# JanusV1.net
KiCad netlist of a schematic drawn in EAGLE
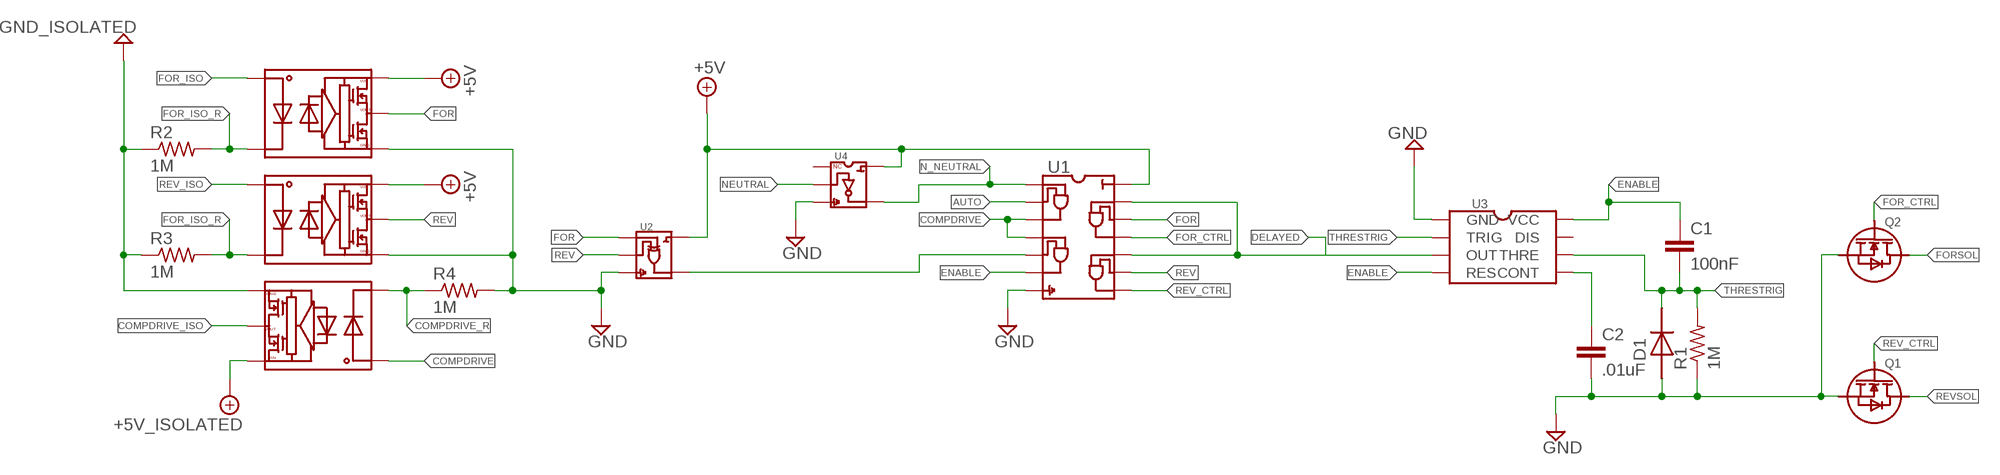
[diagram p0: schematic, sheet 1]

(export (version "E")
  (design (tool "Eeschema 10.0.6"))
  (components
    (comp (ref "C1")
      (value "100nF")
      (footprint "eagle-import:C0603")
      (libsource (lib "eagle-import") (part "C-EUC0603"))
    )
    (comp (ref "C2")
      (value ".01uF")
      (footprint "eagle-import:C0603")
      (libsource (lib "eagle-import") (part "C-EUC0603"))
    )
    (comp (ref "D1")
      (value "1N4148X-TP")
      (footprint "eagle-import:SOD523_SC79")
      (libsource (lib "eagle-import") (part "1N4148X-TP"))
    )
    (comp (ref "OK1")
      (value "TLP152")
      (footprint "eagle-import:6-SOIC-5")
      (libsource (lib "eagle-import") (part "TLP152"))
    )
    (comp (ref "OK2")
      (value "TLP152")
      (footprint "eagle-import:6-SOIC-5")
      (libsource (lib "eagle-import") (part "TLP152"))
    )
    (comp (ref "OK3")
      (value "TLP152")
      (footprint "eagle-import:6-SOIC-5")
      (libsource (lib "eagle-import") (part "TLP152"))
    )
    (comp (ref "Q1")
      (value "DMN6140L-7")
      (footprint "eagle-import:SOT23")
      (libsource (lib "eagle-import") (part "DMN6140L-7"))
    )
    (comp (ref "Q2")
      (value "DMN6140L-7")
      (footprint "eagle-import:SOT23")
      (libsource (lib "eagle-import") (part "DMN6140L-7"))
    )
    (comp (ref "R1")
      (value "1M")
      (footprint "eagle-import:R0603")
      (libsource (lib "eagle-import") (part "R-US_R0603"))
    )
    (comp (ref "R2")
      (value "1M")
      (footprint "eagle-import:R0603")
      (libsource (lib "eagle-import") (part "R-US_R0603"))
    )
    (comp (ref "R3")
      (value "1M")
      (footprint "eagle-import:R0603")
      (libsource (lib "eagle-import") (part "R-US_R0603"))
    )
    (comp (ref "R4")
      (value "1M")
      (footprint "eagle-import:R0603")
      (libsource (lib "eagle-import") (part "R-US_R0603"))
    )
    (comp (ref "U1")
      (value "SN74LV08APWR")
      (footprint "eagle-import:TSSOP-14")
      (libsource (lib "eagle-import") (part "SN74LV08APWR"))
    )
    (comp (ref "U2")
      (value "74LVC1G86W5-7")
      (footprint "eagle-import:SOT-25")
      (libsource (lib "eagle-import") (part "74LVC1G86W5-7"))
    )
    (comp (ref "U3")
      (value "NE555S-13DICT-ND")
      (footprint "eagle-import:SO-8")
      (libsource (lib "eagle-import") (part "NE555S-13DICT-ND"))
    )
    (comp (ref "U4")
      (value "74HCT1G14GW,125")
      (footprint "eagle-import:SOT-353")
      (libsource (lib "eagle-import") (part "74HCT1G14GW,125"))
    )
  )
  (nets
    (net (code "1") (name "+5V") (class "Default")
      (node (ref "OK1") (pin "P$6") (pinfunction "P$6_P$6") (pintype "bidirectional"))
      (node (ref "OK2") (pin "P$6") (pinfunction "P$6_P$6") (pintype "bidirectional"))
      (node (ref "OK3") (pin "P$6") (pinfunction "P$6_P$6") (pintype "bidirectional"))
      (node (ref "U1") (pin "P$14") (pinfunction "P$14_P$14") (pintype "bidirectional"))
      (node (ref "U2") (pin "P$5") (pinfunction "P$5_P$5") (pintype "bidirectional"))
      (node (ref "U4") (pin "P$5") (pinfunction "P$5_P$5") (pintype "bidirectional"))
    )
    (net (code "2") (name "AUTO") (class "Default")
      (node (ref "U1") (pin "P$2") (pinfunction "P$2_P$2") (pintype "bidirectional"))
    )
    (net (code "3") (name "COMPDRIVE") (class "Default")
      (node (ref "OK3") (pin "P$1") (pinfunction "P$1_P$1") (pintype "bidirectional"))
      (node (ref "U1") (pin "P$3") (pinfunction "P$3_P$3") (pintype "bidirectional"))
      (node (ref "U1") (pin "P$4") (pinfunction "P$4_P$4") (pintype "bidirectional"))
    )
    (net (code "4") (name "COMPDRIVE_ISO") (class "Default")
      (node (ref "OK3") (pin "P$5") (pinfunction "P$5_P$5") (pintype "bidirectional"))
    )
    (net (code "5") (name "COMPDRIVE_R") (class "Default")
      (node (ref "OK3") (pin "P$3") (pinfunction "P$2_P$3") (pintype "bidirectional"))
      (node (ref "R4") (pin "1") (pinfunction "1_1") (pintype "passive"))
    )
    (net (code "6") (name "DELAYED") (class "Default")
      (node (ref "U1") (pin "P$10") (pinfunction "P$10_P$10") (pintype "bidirectional"))
      (node (ref "U1") (pin "P$13") (pinfunction "P$13_P$13") (pintype "bidirectional"))
      (node (ref "U3") (pin "P$3") (pinfunction "OUT_P$3") (pintype "bidirectional"))
    )
    (net (code "7") (name "ENABLE") (class "Default")
      (node (ref "C1") (pin "1") (pinfunction "1_1") (pintype "passive"))
      (node (ref "U1") (pin "P$6") (pinfunction "P$6_P$6") (pintype "bidirectional"))
      (node (ref "U3") (pin "P$4") (pinfunction "RES_P$4") (pintype "bidirectional"))
      (node (ref "U3") (pin "P$8") (pinfunction "VCC_P$8") (pintype "bidirectional"))
    )
    (net (code "8") (name "FOR") (class "Default")
      (node (ref "OK1") (pin "P$5") (pinfunction "P$5_P$5") (pintype "bidirectional"))
      (node (ref "U1") (pin "P$12") (pinfunction "P$12_P$12") (pintype "bidirectional"))
      (node (ref "U2") (pin "P$1") (pinfunction "P$1_P$1") (pintype "bidirectional"))
    )
    (net (code "9") (name "FORSOL") (class "Default")
      (node (ref "Q2") (pin "P$3") (pinfunction "D_P$3") (pintype "bidirectional"))
    )
    (net (code "10") (name "FOR_CTRL") (class "Default")
      (node (ref "Q2") (pin "P$1") (pinfunction "G_P$1") (pintype "bidirectional"))
      (node (ref "U1") (pin "P$11") (pinfunction "P$11_P$11") (pintype "bidirectional"))
    )
    (net (code "11") (name "FOR_ISO") (class "Default")
      (node (ref "OK1") (pin "P$1") (pinfunction "P$1_P$1") (pintype "bidirectional"))
    )
    (net (code "12") (name "FOR_ISO_R") (class "Default")
      (node (ref "OK1") (pin "P$3") (pinfunction "P$2_P$3") (pintype "bidirectional"))
      (node (ref "OK2") (pin "P$3") (pinfunction "P$2_P$3") (pintype "bidirectional"))
      (node (ref "R2") (pin "2") (pinfunction "2_2") (pintype "passive"))
      (node (ref "R3") (pin "2") (pinfunction "2_2") (pintype "passive"))
    )
    (net (code "13") (name "GND") (class "Default")
      (node (ref "C2") (pin "2") (pinfunction "2_2") (pintype "passive"))
      (node (ref "D1") (pin "P$1") (pinfunction "P$1_P$1") (pintype "bidirectional"))
      (node (ref "OK1") (pin "P$4") (pinfunction "P$4_P$4") (pintype "bidirectional"))
      (node (ref "OK2") (pin "P$4") (pinfunction "P$4_P$4") (pintype "bidirectional"))
      (node (ref "OK3") (pin "P$4") (pinfunction "P$4_P$4") (pintype "bidirectional"))
      (node (ref "Q1") (pin "P$2") (pinfunction "S_P$2") (pintype "bidirectional"))
      (node (ref "Q2") (pin "P$2") (pinfunction "S_P$2") (pintype "bidirectional"))
      (node (ref "R1") (pin "1") (pinfunction "1_1") (pintype "passive"))
      (node (ref "R2") (pin "1") (pinfunction "1_1") (pintype "passive"))
      (node (ref "R3") (pin "1") (pinfunction "1_1") (pintype "passive"))
      (node (ref "R4") (pin "2") (pinfunction "2_2") (pintype "passive"))
      (node (ref "U1") (pin "P$7") (pinfunction "P$7_P$7") (pintype "bidirectional"))
      (node (ref "U2") (pin "P$3") (pinfunction "P$3_P$3") (pintype "bidirectional"))
      (node (ref "U3") (pin "P$1") (pinfunction "GND_P$1") (pintype "bidirectional"))
      (node (ref "U4") (pin "P$3") (pinfunction "P$3_P$3") (pintype "bidirectional"))
    )
    (net (code "14") (name "NEUTRAL") (class "Default")
      (node (ref "U4") (pin "P$2") (pinfunction "P$2_P$2") (pintype "bidirectional"))
    )
    (net (code "15") (name "N_NEUTRAL") (class "Default")
      (node (ref "U1") (pin "P$1") (pinfunction "P$1_P$1") (pintype "bidirectional"))
      (node (ref "U4") (pin "P$4") (pinfunction "P$4_P$4") (pintype "bidirectional"))
    )
    (net (code "16") (name "Net-(U1-PadP$5)") (class "Default")
      (node (ref "U1") (pin "P$5") (pinfunction "P$5_P$5") (pintype "bidirectional"))
      (node (ref "U2") (pin "P$4") (pinfunction "P$4_P$4") (pintype "bidirectional"))
    )
    (net (code "17") (name "Net-(U3-CONT)") (class "Default")
      (node (ref "C2") (pin "1") (pinfunction "1_1") (pintype "passive"))
      (node (ref "U3") (pin "P$5") (pinfunction "CONT_P$5") (pintype "bidirectional"))
    )
    (net (code "18") (name "REV") (class "Default")
      (node (ref "OK2") (pin "P$5") (pinfunction "P$5_P$5") (pintype "bidirectional"))
      (node (ref "U1") (pin "P$9") (pinfunction "P$9_P$9") (pintype "bidirectional"))
      (node (ref "U2") (pin "P$2") (pinfunction "P$2_P$2") (pintype "bidirectional"))
    )
    (net (code "19") (name "REVSOL") (class "Default")
      (node (ref "Q1") (pin "P$3") (pinfunction "D_P$3") (pintype "bidirectional"))
    )
    (net (code "20") (name "REV_CTRL") (class "Default")
      (node (ref "Q1") (pin "P$1") (pinfunction "G_P$1") (pintype "bidirectional"))
      (node (ref "U1") (pin "P$8") (pinfunction "P$8_P$8") (pintype "bidirectional"))
    )
    (net (code "21") (name "REV_ISO") (class "Default")
      (node (ref "OK2") (pin "P$1") (pinfunction "P$1_P$1") (pintype "bidirectional"))
    )
    (net (code "22") (name "THRESTRIG") (class "Default")
      (node (ref "C1") (pin "2") (pinfunction "2_2") (pintype "passive"))
      (node (ref "D1") (pin "P$2") (pinfunction "P$2_P$2") (pintype "bidirectional"))
      (node (ref "R1") (pin "2") (pinfunction "2_2") (pintype "passive"))
      (node (ref "U3") (pin "P$2") (pinfunction "TRIG_P$2") (pintype "bidirectional"))
      (node (ref "U3") (pin "P$6") (pinfunction "THRE_P$6") (pintype "bidirectional"))
    )
    (net (code "23") (name "unconnected-(U3-DIS-PadP$7)") (class "Default")
      (node (ref "U3") (pin "P$7") (pinfunction "DIS_P$7") (pintype "bidirectional"))
    )
    (net (code "24") (name "unconnected-(U4-PadP$1)") (class "Default")
      (node (ref "U4") (pin "P$1") (pinfunction "P$1_P$1") (pintype "bidirectional"))
    )
  )
)
